# noninverting_amplifier.net
KiCad netlist of a schematic drawn in EAGLE
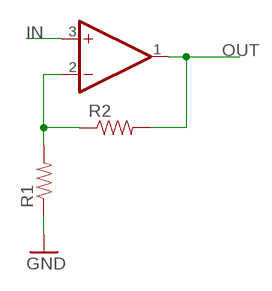
[diagram p0: schematic, sheet 1]

(export (version "E")
  (design (tool "Eeschema 10.0.6"))
  (components
    (comp (ref "IC1")
      (value "MCP6022")
      (footprint "eagle-import:SOIC8_150MIL")
      (libsource (lib "eagle-import") (part "MCP6022"))
    )
    (comp (ref "R1")
      (value "RESISTOR0402-RES")
      (footprint "eagle-import:0402-RES")
      (libsource (lib "eagle-import") (part "RESISTOR0402-RES"))
    )
    (comp (ref "R2")
      (value "RESISTOR0402-RES")
      (footprint "eagle-import:0402-RES")
      (libsource (lib "eagle-import") (part "RESISTOR0402-RES"))
    )
  )
  (nets
    (net (code "1") (name "/IN") (class "Default")
      (node (ref "IC1") (pin "3") (pinfunction "+IN_3") (pintype "input"))
    )
    (net (code "2") (name "/OUT") (class "Default")
      (node (ref "IC1") (pin "1") (pinfunction "OUT_1") (pintype "output"))
      (node (ref "R2") (pin "2") (pinfunction "2_2") (pintype "passive"))
    )
    (net (code "3") (name "GND") (class "Default")
      (node (ref "R1") (pin "1") (pinfunction "1_1") (pintype "passive"))
    )
    (net (code "4") (name "Net-(IC1A--IN)") (class "Default")
      (node (ref "IC1") (pin "2") (pinfunction "-IN_2") (pintype "input"))
      (node (ref "R1") (pin "2") (pinfunction "2_2") (pintype "passive"))
      (node (ref "R2") (pin "1") (pinfunction "1_1") (pintype "passive"))
    )
  )
)
